# Pendant.net
KiCad netlist of a schematic drawn in EAGLE
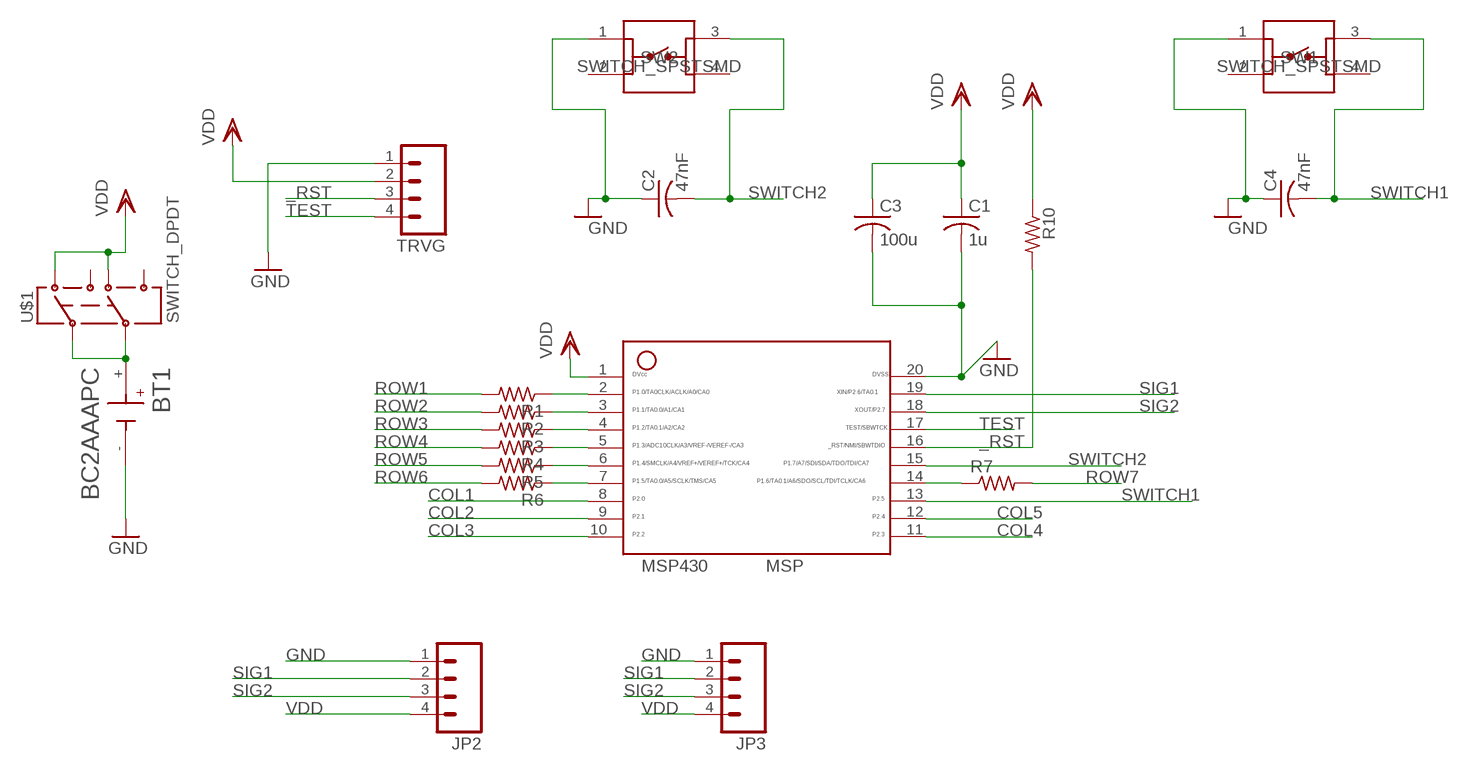
[diagram p0: schematic, sheet 1]
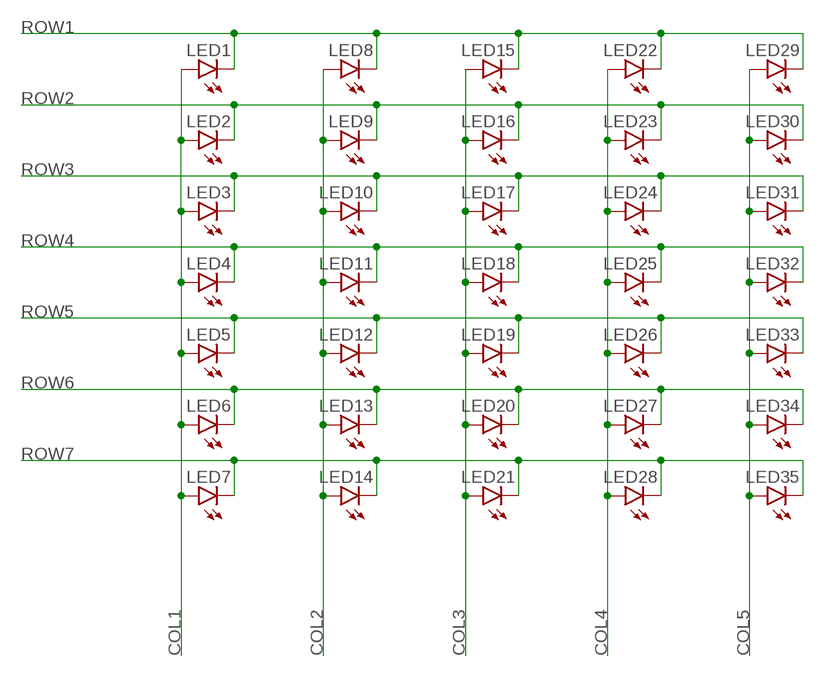
[diagram p1: schematic, sheet 2]

(export (version "E")
  (design (tool "Eeschema 10.0.6"))
  (components
    (comp (ref "LED1")
      (value "LEDSML1206")
      (footprint "eagle-import:SML1206")
      (libsource (lib "eagle-import") (part "LEDSML1206"))
    )
    (comp (ref "LED2")
      (value "LEDSML1206")
      (footprint "eagle-import:SML1206")
      (libsource (lib "eagle-import") (part "LEDSML1206"))
    )
    (comp (ref "LED3")
      (value "LEDSML1206")
      (footprint "eagle-import:SML1206")
      (libsource (lib "eagle-import") (part "LEDSML1206"))
    )
    (comp (ref "LED4")
      (value "LEDSML1206")
      (footprint "eagle-import:SML1206")
      (libsource (lib "eagle-import") (part "LEDSML1206"))
    )
    (comp (ref "LED5")
      (value "LEDSML1206")
      (footprint "eagle-import:SML1206")
      (libsource (lib "eagle-import") (part "LEDSML1206"))
    )
    (comp (ref "LED6")
      (value "LEDSML1206")
      (footprint "eagle-import:SML1206")
      (libsource (lib "eagle-import") (part "LEDSML1206"))
    )
    (comp (ref "LED7")
      (value "LEDSML1206")
      (footprint "eagle-import:SML1206")
      (libsource (lib "eagle-import") (part "LEDSML1206"))
    )
    (comp (ref "LED8")
      (value "LEDSML1206")
      (footprint "eagle-import:SML1206")
      (libsource (lib "eagle-import") (part "LEDSML1206"))
    )
    (comp (ref "LED9")
      (value "LEDSML1206")
      (footprint "eagle-import:SML1206")
      (libsource (lib "eagle-import") (part "LEDSML1206"))
    )
    (comp (ref "LED10")
      (value "LEDSML1206")
      (footprint "eagle-import:SML1206")
      (libsource (lib "eagle-import") (part "LEDSML1206"))
    )
    (comp (ref "LED11")
      (value "LEDSML1206")
      (footprint "eagle-import:SML1206")
      (libsource (lib "eagle-import") (part "LEDSML1206"))
    )
    (comp (ref "LED12")
      (value "LEDSML1206")
      (footprint "eagle-import:SML1206")
      (libsource (lib "eagle-import") (part "LEDSML1206"))
    )
    (comp (ref "LED13")
      (value "LEDSML1206")
      (footprint "eagle-import:SML1206")
      (libsource (lib "eagle-import") (part "LEDSML1206"))
    )
    (comp (ref "LED14")
      (value "LEDSML1206")
      (footprint "eagle-import:SML1206")
      (libsource (lib "eagle-import") (part "LEDSML1206"))
    )
    (comp (ref "LED15")
      (value "LEDSML1206")
      (footprint "eagle-import:SML1206")
      (libsource (lib "eagle-import") (part "LEDSML1206"))
    )
    (comp (ref "LED16")
      (value "LEDSML1206")
      (footprint "eagle-import:SML1206")
      (libsource (lib "eagle-import") (part "LEDSML1206"))
    )
    (comp (ref "LED17")
      (value "LEDSML1206")
      (footprint "eagle-import:SML1206")
      (libsource (lib "eagle-import") (part "LEDSML1206"))
    )
    (comp (ref "LED18")
      (value "LEDSML1206")
      (footprint "eagle-import:SML1206")
      (libsource (lib "eagle-import") (part "LEDSML1206"))
    )
    (comp (ref "LED19")
      (value "LEDSML1206")
      (footprint "eagle-import:SML1206")
      (libsource (lib "eagle-import") (part "LEDSML1206"))
    )
    (comp (ref "LED20")
      (value "LEDSML1206")
      (footprint "eagle-import:SML1206")
      (libsource (lib "eagle-import") (part "LEDSML1206"))
    )
    (comp (ref "LED21")
      (value "LEDSML1206")
      (footprint "eagle-import:SML1206")
      (libsource (lib "eagle-import") (part "LEDSML1206"))
    )
    (comp (ref "LED22")
      (value "LEDSML1206")
      (footprint "eagle-import:SML1206")
      (libsource (lib "eagle-import") (part "LEDSML1206"))
    )
    (comp (ref "LED23")
      (value "LEDSML1206")
      (footprint "eagle-import:SML1206")
      (libsource (lib "eagle-import") (part "LEDSML1206"))
    )
    (comp (ref "LED24")
      (value "LEDSML1206")
      (footprint "eagle-import:SML1206")
      (libsource (lib "eagle-import") (part "LEDSML1206"))
    )
    (comp (ref "LED25")
      (value "LEDSML1206")
      (footprint "eagle-import:SML1206")
      (libsource (lib "eagle-import") (part "LEDSML1206"))
    )
    (comp (ref "LED26")
      (value "LEDSML1206")
      (footprint "eagle-import:SML1206")
      (libsource (lib "eagle-import") (part "LEDSML1206"))
    )
    (comp (ref "LED27")
      (value "LEDSML1206")
      (footprint "eagle-import:SML1206")
      (libsource (lib "eagle-import") (part "LEDSML1206"))
    )
    (comp (ref "LED28")
      (value "LEDSML1206")
      (footprint "eagle-import:SML1206")
      (libsource (lib "eagle-import") (part "LEDSML1206"))
    )
    (comp (ref "LED29")
      (value "LEDSML1206")
      (footprint "eagle-import:SML1206")
      (libsource (lib "eagle-import") (part "LEDSML1206"))
    )
    (comp (ref "LED30")
      (value "LEDSML1206")
      (footprint "eagle-import:SML1206")
      (libsource (lib "eagle-import") (part "LEDSML1206"))
    )
    (comp (ref "LED31")
      (value "LEDSML1206")
      (footprint "eagle-import:SML1206")
      (libsource (lib "eagle-import") (part "LEDSML1206"))
    )
    (comp (ref "LED32")
      (value "LEDSML1206")
      (footprint "eagle-import:SML1206")
      (libsource (lib "eagle-import") (part "LEDSML1206"))
    )
    (comp (ref "LED33")
      (value "LEDSML1206")
      (footprint "eagle-import:SML1206")
      (libsource (lib "eagle-import") (part "LEDSML1206"))
    )
    (comp (ref "LED34")
      (value "LEDSML1206")
      (footprint "eagle-import:SML1206")
      (libsource (lib "eagle-import") (part "LEDSML1206"))
    )
    (comp (ref "LED35")
      (value "LEDSML1206")
      (footprint "eagle-import:SML1206")
      (libsource (lib "eagle-import") (part "LEDSML1206"))
    )
    (comp (ref "BT1")
      (value "BC2AAAPC")
      (footprint "eagle-import:BAT_BC2AAAPC")
      (fields (field (name "DIGI-KEY_PART_NUMBER") "BC2AAAPC-ND") (field (name "MF") "MPD"))
      (libsource (lib "eagle-import") (part "BC2AAAPC"))
    )
    (comp (ref "C1")
      (value "1u")
      (footprint "eagle-import:C0603")
      (libsource (lib "eagle-import") (part "C-USC0603"))
    )
    (comp (ref "C2")
      (value "47nF")
      (footprint "eagle-import:C0603")
      (libsource (lib "eagle-import") (part "C-USC0603"))
    )
    (comp (ref "C3")
      (value "100u")
      (footprint "eagle-import:C1206")
      (libsource (lib "eagle-import") (part "C-USC1206"))
    )
    (comp (ref "C4")
      (value "47nF")
      (footprint "eagle-import:C0603")
      (libsource (lib "eagle-import") (part "C-USC0603"))
    )
    (comp (ref "JP2")
      (value "M04LOCK")
      (footprint "eagle-import:1X04_LOCK")
      (libsource (lib "eagle-import") (part "M04LOCK"))
    )
    (comp (ref "JP3")
      (value "M04LOCK")
      (footprint "eagle-import:1X04_LOCK")
      (libsource (lib "eagle-import") (part "M04LOCK"))
    )
    (comp (ref "MSP430")
      (value "MSP")
      (footprint "eagle-import:20_PIN")
      (libsource (lib "eagle-import") (part "MSP430"))
    )
    (comp (ref "R1")
      (value "R-US_R0402")
      (footprint "eagle-import:R0402")
      (libsource (lib "eagle-import") (part "R-US_R0402"))
    )
    (comp (ref "R2")
      (value "R-US_R0402")
      (footprint "eagle-import:R0402")
      (libsource (lib "eagle-import") (part "R-US_R0402"))
    )
    (comp (ref "R3")
      (value "R-US_R0402")
      (footprint "eagle-import:R0402")
      (libsource (lib "eagle-import") (part "R-US_R0402"))
    )
    (comp (ref "R4")
      (value "R-US_R0402")
      (footprint "eagle-import:R0402")
      (libsource (lib "eagle-import") (part "R-US_R0402"))
    )
    (comp (ref "R5")
      (value "R-US_R0402")
      (footprint "eagle-import:R0402")
      (libsource (lib "eagle-import") (part "R-US_R0402"))
    )
    (comp (ref "R6")
      (value "R-US_R0402")
      (footprint "eagle-import:R0402")
      (libsource (lib "eagle-import") (part "R-US_R0402"))
    )
    (comp (ref "R7")
      (value "R-US_R0402")
      (footprint "eagle-import:R0402")
      (libsource (lib "eagle-import") (part "R-US_R0402"))
    )
    (comp (ref "R10")
      (value "R-US_R0402")
      (footprint "eagle-import:R0402")
      (libsource (lib "eagle-import") (part "R-US_R0402"))
    )
    (comp (ref "SW1")
      (value "SWITCH_SPSTSMD")
      (footprint "eagle-import:SW_1571563-4")
      (libsource (lib "eagle-import") (part "SWITCH_SPSTSMD"))
    )
    (comp (ref "SW2")
      (value "SWITCH_SPSTSMD")
      (footprint "eagle-import:SW_1571563-4")
      (libsource (lib "eagle-import") (part "SWITCH_SPSTSMD"))
    )
    (comp (ref "TRVG")
      (value "M04LOCK")
      (footprint "eagle-import:1X04_LOCK")
      (libsource (lib "eagle-import") (part "M04LOCK"))
    )
    (comp (ref "U$1")
      (value "SWITCH_DPDT")
      (footprint "eagle-import:JS_DPDT_TH")
      (libsource (lib "eagle-import") (part "SWITCH_DPDT"))
    )
  )
  (nets
    (net (code "1") (name "COL1") (class "Default")
      (node (ref "LED1") (pin "A") (pinfunction "A_A") (pintype "passive"))
      (node (ref "LED2") (pin "A") (pinfunction "A_A") (pintype "passive"))
      (node (ref "LED3") (pin "A") (pinfunction "A_A") (pintype "passive"))
      (node (ref "LED4") (pin "A") (pinfunction "A_A") (pintype "passive"))
      (node (ref "LED5") (pin "A") (pinfunction "A_A") (pintype "passive"))
      (node (ref "LED6") (pin "A") (pinfunction "A_A") (pintype "passive"))
      (node (ref "LED7") (pin "A") (pinfunction "A_A") (pintype "passive"))
      (node (ref "MSP430") (pin "8") (pinfunction "8_8") (pintype "bidirectional"))
    )
    (net (code "2") (name "COL2") (class "Default")
      (node (ref "LED10") (pin "A") (pinfunction "A_A") (pintype "passive"))
      (node (ref "LED11") (pin "A") (pinfunction "A_A") (pintype "passive"))
      (node (ref "LED12") (pin "A") (pinfunction "A_A") (pintype "passive"))
      (node (ref "LED13") (pin "A") (pinfunction "A_A") (pintype "passive"))
      (node (ref "LED14") (pin "A") (pinfunction "A_A") (pintype "passive"))
      (node (ref "LED8") (pin "A") (pinfunction "A_A") (pintype "passive"))
      (node (ref "LED9") (pin "A") (pinfunction "A_A") (pintype "passive"))
      (node (ref "MSP430") (pin "9") (pinfunction "9_9") (pintype "bidirectional"))
    )
    (net (code "3") (name "COL3") (class "Default")
      (node (ref "LED15") (pin "A") (pinfunction "A_A") (pintype "passive"))
      (node (ref "LED16") (pin "A") (pinfunction "A_A") (pintype "passive"))
      (node (ref "LED17") (pin "A") (pinfunction "A_A") (pintype "passive"))
      (node (ref "LED18") (pin "A") (pinfunction "A_A") (pintype "passive"))
      (node (ref "LED19") (pin "A") (pinfunction "A_A") (pintype "passive"))
      (node (ref "LED20") (pin "A") (pinfunction "A_A") (pintype "passive"))
      (node (ref "LED21") (pin "A") (pinfunction "A_A") (pintype "passive"))
      (node (ref "MSP430") (pin "10") (pinfunction "10_10") (pintype "bidirectional"))
    )
    (net (code "4") (name "COL4") (class "Default")
      (node (ref "LED22") (pin "A") (pinfunction "A_A") (pintype "passive"))
      (node (ref "LED23") (pin "A") (pinfunction "A_A") (pintype "passive"))
      (node (ref "LED24") (pin "A") (pinfunction "A_A") (pintype "passive"))
      (node (ref "LED25") (pin "A") (pinfunction "A_A") (pintype "passive"))
      (node (ref "LED26") (pin "A") (pinfunction "A_A") (pintype "passive"))
      (node (ref "LED27") (pin "A") (pinfunction "A_A") (pintype "passive"))
      (node (ref "LED28") (pin "A") (pinfunction "A_A") (pintype "passive"))
      (node (ref "MSP430") (pin "11") (pinfunction "11_11") (pintype "bidirectional"))
    )
    (net (code "5") (name "COL5") (class "Default")
      (node (ref "LED29") (pin "A") (pinfunction "A_A") (pintype "passive"))
      (node (ref "LED30") (pin "A") (pinfunction "A_A") (pintype "passive"))
      (node (ref "LED31") (pin "A") (pinfunction "A_A") (pintype "passive"))
      (node (ref "LED32") (pin "A") (pinfunction "A_A") (pintype "passive"))
      (node (ref "LED33") (pin "A") (pinfunction "A_A") (pintype "passive"))
      (node (ref "LED34") (pin "A") (pinfunction "A_A") (pintype "passive"))
      (node (ref "LED35") (pin "A") (pinfunction "A_A") (pintype "passive"))
      (node (ref "MSP430") (pin "12") (pinfunction "12_12") (pintype "bidirectional"))
    )
    (net (code "6") (name "GND") (class "Default")
      (node (ref "BT1") (pin "-") (pinfunction "-_-") (pintype "passive"))
      (node (ref "C1") (pin "2") (pinfunction "2_2") (pintype "passive"))
      (node (ref "C2") (pin "1") (pinfunction "1_1") (pintype "passive"))
      (node (ref "C3") (pin "2") (pinfunction "2_2") (pintype "passive"))
      (node (ref "C4") (pin "1") (pinfunction "1_1") (pintype "passive"))
      (node (ref "JP2") (pin "1") (pinfunction "1_1") (pintype "passive"))
      (node (ref "JP3") (pin "1") (pinfunction "1_1") (pintype "passive"))
      (node (ref "MSP430") (pin "20") (pinfunction "20_20") (pintype "bidirectional"))
      (node (ref "SW1") (pin "1") (pinfunction "1_1") (pintype "passive"))
      (node (ref "SW2") (pin "1") (pinfunction "1_1") (pintype "passive"))
      (node (ref "TRVG") (pin "1") (pinfunction "1_1") (pintype "passive"))
    )
    (net (code "7") (name "Net-(BT1-Pad+)") (class "Default")
      (node (ref "BT1") (pin "+") (pinfunction "+_+") (pintype "passive"))
      (node (ref "U$1") (pin "2") (pinfunction "2_2") (pintype "bidirectional"))
      (node (ref "U$1") (pin "5") (pinfunction "5_5") (pintype "bidirectional"))
    )
    (net (code "8") (name "Net-(MSP430-Pad2)") (class "Default")
      (node (ref "MSP430") (pin "2") (pinfunction "2_2") (pintype "bidirectional"))
      (node (ref "R1") (pin "1") (pinfunction "1_1") (pintype "passive"))
    )
    (net (code "9") (name "Net-(MSP430-Pad3)") (class "Default")
      (node (ref "MSP430") (pin "3") (pinfunction "3_3") (pintype "bidirectional"))
      (node (ref "R2") (pin "1") (pinfunction "1_1") (pintype "passive"))
    )
    (net (code "10") (name "Net-(MSP430-Pad4)") (class "Default")
      (node (ref "MSP430") (pin "4") (pinfunction "4_4") (pintype "bidirectional"))
      (node (ref "R3") (pin "1") (pinfunction "1_1") (pintype "passive"))
    )
    (net (code "11") (name "Net-(MSP430-Pad5)") (class "Default")
      (node (ref "MSP430") (pin "5") (pinfunction "5_5") (pintype "bidirectional"))
      (node (ref "R4") (pin "1") (pinfunction "1_1") (pintype "passive"))
    )
    (net (code "12") (name "Net-(MSP430-Pad6)") (class "Default")
      (node (ref "MSP430") (pin "6") (pinfunction "6_6") (pintype "bidirectional"))
      (node (ref "R5") (pin "1") (pinfunction "1_1") (pintype "passive"))
    )
    (net (code "13") (name "Net-(MSP430-Pad7)") (class "Default")
      (node (ref "MSP430") (pin "7") (pinfunction "7_7") (pintype "bidirectional"))
      (node (ref "R6") (pin "1") (pinfunction "1_1") (pintype "passive"))
    )
    (net (code "14") (name "Net-(MSP430-Pad14)") (class "Default")
      (node (ref "MSP430") (pin "14") (pinfunction "14_14") (pintype "bidirectional"))
      (node (ref "R7") (pin "1") (pinfunction "1_1") (pintype "passive"))
    )
    (net (code "15") (name "ROW1") (class "Default")
      (node (ref "LED1") (pin "C") (pinfunction "C_C") (pintype "passive"))
      (node (ref "LED15") (pin "C") (pinfunction "C_C") (pintype "passive"))
      (node (ref "LED22") (pin "C") (pinfunction "C_C") (pintype "passive"))
      (node (ref "LED29") (pin "C") (pinfunction "C_C") (pintype "passive"))
      (node (ref "LED8") (pin "C") (pinfunction "C_C") (pintype "passive"))
      (node (ref "R1") (pin "2") (pinfunction "2_2") (pintype "passive"))
    )
    (net (code "16") (name "ROW2") (class "Default")
      (node (ref "LED16") (pin "C") (pinfunction "C_C") (pintype "passive"))
      (node (ref "LED2") (pin "C") (pinfunction "C_C") (pintype "passive"))
      (node (ref "LED23") (pin "C") (pinfunction "C_C") (pintype "passive"))
      (node (ref "LED30") (pin "C") (pinfunction "C_C") (pintype "passive"))
      (node (ref "LED9") (pin "C") (pinfunction "C_C") (pintype "passive"))
      (node (ref "R2") (pin "2") (pinfunction "2_2") (pintype "passive"))
    )
    (net (code "17") (name "ROW3") (class "Default")
      (node (ref "LED10") (pin "C") (pinfunction "C_C") (pintype "passive"))
      (node (ref "LED17") (pin "C") (pinfunction "C_C") (pintype "passive"))
      (node (ref "LED24") (pin "C") (pinfunction "C_C") (pintype "passive"))
      (node (ref "LED3") (pin "C") (pinfunction "C_C") (pintype "passive"))
      (node (ref "LED31") (pin "C") (pinfunction "C_C") (pintype "passive"))
      (node (ref "R3") (pin "2") (pinfunction "2_2") (pintype "passive"))
    )
    (net (code "18") (name "ROW4") (class "Default")
      (node (ref "LED11") (pin "C") (pinfunction "C_C") (pintype "passive"))
      (node (ref "LED18") (pin "C") (pinfunction "C_C") (pintype "passive"))
      (node (ref "LED25") (pin "C") (pinfunction "C_C") (pintype "passive"))
      (node (ref "LED32") (pin "C") (pinfunction "C_C") (pintype "passive"))
      (node (ref "LED4") (pin "C") (pinfunction "C_C") (pintype "passive"))
      (node (ref "R4") (pin "2") (pinfunction "2_2") (pintype "passive"))
    )
    (net (code "19") (name "ROW5") (class "Default")
      (node (ref "LED12") (pin "C") (pinfunction "C_C") (pintype "passive"))
      (node (ref "LED19") (pin "C") (pinfunction "C_C") (pintype "passive"))
      (node (ref "LED26") (pin "C") (pinfunction "C_C") (pintype "passive"))
      (node (ref "LED33") (pin "C") (pinfunction "C_C") (pintype "passive"))
      (node (ref "LED5") (pin "C") (pinfunction "C_C") (pintype "passive"))
      (node (ref "R5") (pin "2") (pinfunction "2_2") (pintype "passive"))
    )
    (net (code "20") (name "ROW6") (class "Default")
      (node (ref "LED13") (pin "C") (pinfunction "C_C") (pintype "passive"))
      (node (ref "LED20") (pin "C") (pinfunction "C_C") (pintype "passive"))
      (node (ref "LED27") (pin "C") (pinfunction "C_C") (pintype "passive"))
      (node (ref "LED34") (pin "C") (pinfunction "C_C") (pintype "passive"))
      (node (ref "LED6") (pin "C") (pinfunction "C_C") (pintype "passive"))
      (node (ref "R6") (pin "2") (pinfunction "2_2") (pintype "passive"))
    )
    (net (code "21") (name "ROW7") (class "Default")
      (node (ref "LED14") (pin "C") (pinfunction "C_C") (pintype "passive"))
      (node (ref "LED21") (pin "C") (pinfunction "C_C") (pintype "passive"))
      (node (ref "LED28") (pin "C") (pinfunction "C_C") (pintype "passive"))
      (node (ref "LED35") (pin "C") (pinfunction "C_C") (pintype "passive"))
      (node (ref "LED7") (pin "C") (pinfunction "C_C") (pintype "passive"))
      (node (ref "R7") (pin "2") (pinfunction "2_2") (pintype "passive"))
    )
    (net (code "22") (name "SIG1") (class "Default")
      (node (ref "JP2") (pin "2") (pinfunction "2_2") (pintype "passive"))
      (node (ref "JP3") (pin "2") (pinfunction "2_2") (pintype "passive"))
      (node (ref "MSP430") (pin "19") (pinfunction "19_19") (pintype "bidirectional"))
    )
    (net (code "23") (name "SIG2") (class "Default")
      (node (ref "JP2") (pin "3") (pinfunction "3_3") (pintype "passive"))
      (node (ref "JP3") (pin "3") (pinfunction "3_3") (pintype "passive"))
      (node (ref "MSP430") (pin "18") (pinfunction "18_18") (pintype "bidirectional"))
    )
    (net (code "24") (name "SWITCH1") (class "Default")
      (node (ref "C4") (pin "2") (pinfunction "2_2") (pintype "passive"))
      (node (ref "MSP430") (pin "13") (pinfunction "13_13") (pintype "bidirectional"))
      (node (ref "SW1") (pin "3") (pinfunction "3_3") (pintype "passive"))
    )
    (net (code "25") (name "SWITCH2") (class "Default")
      (node (ref "C2") (pin "2") (pinfunction "2_2") (pintype "passive"))
      (node (ref "MSP430") (pin "15") (pinfunction "15_15") (pintype "bidirectional"))
      (node (ref "SW2") (pin "3") (pinfunction "3_3") (pintype "passive"))
    )
    (net (code "26") (name "TEST") (class "Default")
      (node (ref "MSP430") (pin "17") (pinfunction "17_17") (pintype "bidirectional"))
      (node (ref "TRVG") (pin "4") (pinfunction "4_4") (pintype "passive"))
    )
    (net (code "27") (name "VDD") (class "Default")
      (node (ref "C1") (pin "1") (pinfunction "1_1") (pintype "passive"))
      (node (ref "C3") (pin "1") (pinfunction "1_1") (pintype "passive"))
      (node (ref "JP2") (pin "4") (pinfunction "4_4") (pintype "passive"))
      (node (ref "JP3") (pin "4") (pinfunction "4_4") (pintype "passive"))
      (node (ref "MSP430") (pin "1") (pinfunction "1_1") (pintype "bidirectional"))
      (node (ref "R10") (pin "1") (pinfunction "1_1") (pintype "passive"))
      (node (ref "TRVG") (pin "2") (pinfunction "2_2") (pintype "passive"))
      (node (ref "U$1") (pin "1") (pinfunction "1_1") (pintype "bidirectional"))
      (node (ref "U$1") (pin "4") (pinfunction "4_4") (pintype "bidirectional"))
    )
    (net (code "28") (name "_RST") (class "Default")
      (node (ref "MSP430") (pin "16") (pinfunction "16_16") (pintype "bidirectional"))
      (node (ref "R10") (pin "2") (pinfunction "2_2") (pintype "passive"))
      (node (ref "TRVG") (pin "3") (pinfunction "3_3") (pintype "passive"))
    )
    (net (code "29") (name "unconnected-(SW1-Pad2)") (class "Default")
      (node (ref "SW1") (pin "2") (pinfunction "2_2") (pintype "passive"))
    )
    (net (code "30") (name "unconnected-(SW1-Pad4)") (class "Default")
      (node (ref "SW1") (pin "4") (pinfunction "4_4") (pintype "passive"))
    )
    (net (code "31") (name "unconnected-(SW2-Pad2)") (class "Default")
      (node (ref "SW2") (pin "2") (pinfunction "2_2") (pintype "passive"))
    )
    (net (code "32") (name "unconnected-(SW2-Pad4)") (class "Default")
      (node (ref "SW2") (pin "4") (pinfunction "4_4") (pintype "passive"))
    )
    (net (code "33") (name "unconnected-(U$1-Pad3)") (class "Default")
      (node (ref "U$1") (pin "3") (pinfunction "3_3") (pintype "bidirectional"))
    )
    (net (code "34") (name "unconnected-(U$1-Pad6)") (class "Default")
      (node (ref "U$1") (pin "6") (pinfunction "6_6") (pintype "bidirectional"))
    )
  )
)
